# 03-Front_Panel_SFP_1.net
KiCad netlist of a schematic drawn in Altium Designer
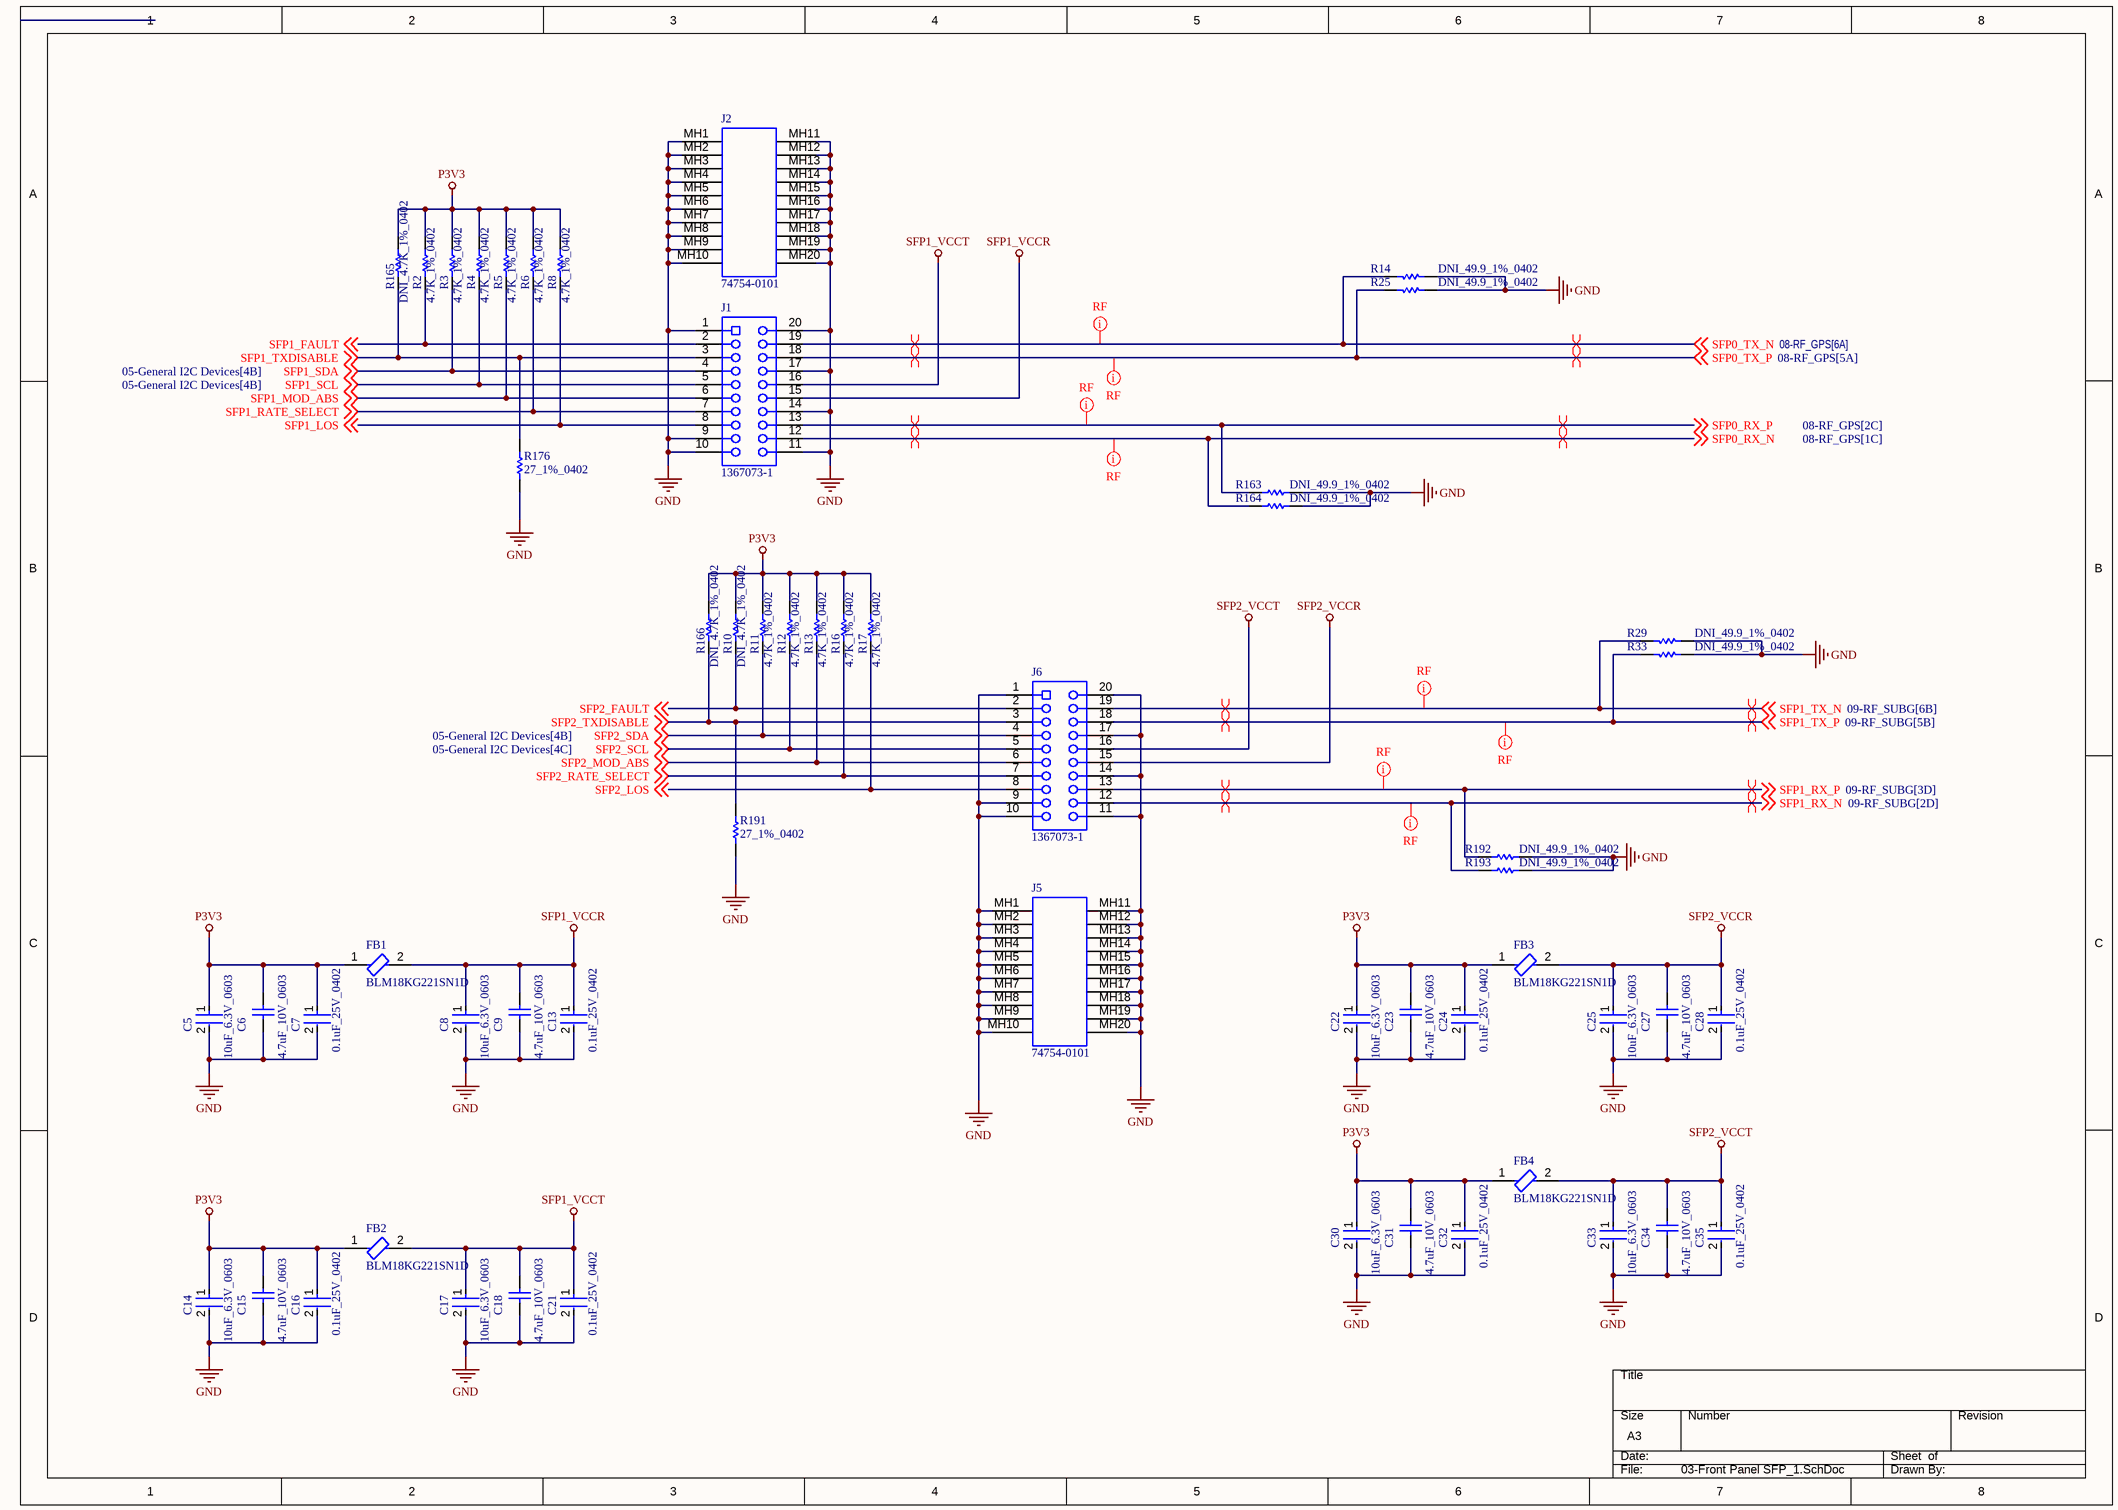
[diagram p0: 03-Front Panel SFP_1.SchDoc]

(export (version "E")
  (design (tool "Eeschema 10.0.6"))
  (components
    (comp (ref "C5")
      (value "10uF_6.3V_0603")
      (footprint "FP-C0603C106M9PACTU-MFG")
      (description "CAP CER 10UF 6.3V X5R 0603")
      (fields
        (field (name "MANUFACTURER PART NUMBER") "C0603C106M9PACTU")
        (field (name "MANUFACTURER") "Kemet")
      )
      (libsource (lib "Altium Content Vault") (part "b4654b650e69147ec39a6b967a45e02"))
    )
    (comp (ref "C6")
      (value "4.7uF_10V_0603")
      (footprint "CAPC1608X87X35NL15T15")
      (fields (field (name "PART NUMBER") "C0603C475K8PACTU") (field (name "MANUFACTURER") "Kemet"))
      (libsource (lib "Altium Content Vault") (part "CAP"))
    )
    (comp (ref "C7")
      (value "0.1uF_25V_0402")
      (footprint "FP-0402-L_1_0_1-W_0_5_0_1-IPC_C")
      (description "General Purpose Ceramic Capacitor, 0402, 100nF, 10%, X7R, 15%, 25V")
      (fields (field (name "VOLTAGE") "25V") (field (name "TOLERANCE") "10%"))
      (libsource (lib "Altium Content Vault") (part "b4654b650e69147ec39a6b967a45e02"))
    )
    (comp (ref "C8")
      (value "10uF_6.3V_0603")
      (footprint "FP-C0603C106M9PACTU-MFG")
      (description "CAP CER 10UF 6.3V X5R 0603")
      (fields
        (field (name "MANUFACTURER PART NUMBER") "C0603C106M9PACTU")
        (field (name "MANUFACTURER") "Kemet")
      )
      (libsource (lib "Altium Content Vault") (part "b4654b650e69147ec39a6b967a45e02"))
    )
    (comp (ref "C9")
      (value "4.7uF_10V_0603")
      (footprint "CAPC1608X87X35NL15T15")
      (fields (field (name "PART NUMBER") "C0603C475K8PACTU") (field (name "MANUFACTURER") "Kemet"))
      (libsource (lib "Altium Content Vault") (part "CAP"))
    )
    (comp (ref "C13")
      (value "0.1uF_25V_0402")
      (footprint "FP-0402-L_1_0_1-W_0_5_0_1-IPC_C")
      (description "General Purpose Ceramic Capacitor, 0402, 100nF, 10%, X7R, 15%, 25V")
      (fields (field (name "VOLTAGE") "25V") (field (name "TOLERANCE") "10%"))
      (libsource (lib "Altium Content Vault") (part "b4654b650e69147ec39a6b967a45e02"))
    )
    (comp (ref "C14")
      (value "10uF_6.3V_0603")
      (footprint "FP-C0603C106M9PACTU-MFG")
      (description "CAP CER 10UF 6.3V X5R 0603")
      (fields
        (field (name "MANUFACTURER PART NUMBER") "C0603C106M9PACTU")
        (field (name "MANUFACTURER") "Kemet")
      )
      (libsource (lib "Altium Content Vault") (part "b4654b650e69147ec39a6b967a45e02"))
    )
    (comp (ref "C15")
      (value "4.7uF_10V_0603")
      (footprint "CAPC1608X87X35NL15T15")
      (fields (field (name "PART NUMBER") "C0603C475K8PACTU") (field (name "MANUFACTURER") "Kemet"))
      (libsource (lib "Altium Content Vault") (part "CAP"))
    )
    (comp (ref "C16")
      (value "0.1uF_25V_0402")
      (footprint "FP-0402-L_1_0_1-W_0_5_0_1-IPC_C")
      (description "General Purpose Ceramic Capacitor, 0402, 100nF, 10%, X7R, 15%, 25V")
      (fields (field (name "VOLTAGE") "25V") (field (name "TOLERANCE") "10%"))
      (libsource (lib "Altium Content Vault") (part "b4654b650e69147ec39a6b967a45e02"))
    )
    (comp (ref "C17")
      (value "10uF_6.3V_0603")
      (footprint "FP-C0603C106M9PACTU-MFG")
      (description "CAP CER 10UF 6.3V X5R 0603")
      (fields
        (field (name "MANUFACTURER PART NUMBER") "C0603C106M9PACTU")
        (field (name "MANUFACTURER") "Kemet")
      )
      (libsource (lib "Altium Content Vault") (part "b4654b650e69147ec39a6b967a45e02"))
    )
    (comp (ref "C18")
      (value "4.7uF_10V_0603")
      (footprint "CAPC1608X87X35NL15T15")
      (fields (field (name "PART NUMBER") "C0603C475K8PACTU") (field (name "MANUFACTURER") "Kemet"))
      (libsource (lib "Altium Content Vault") (part "CAP"))
    )
    (comp (ref "C21")
      (value "0.1uF_25V_0402")
      (footprint "FP-0402-L_1_0_1-W_0_5_0_1-IPC_C")
      (description "General Purpose Ceramic Capacitor, 0402, 100nF, 10%, X7R, 15%, 25V")
      (fields (field (name "VOLTAGE") "25V") (field (name "TOLERANCE") "10%"))
      (libsource (lib "Altium Content Vault") (part "b4654b650e69147ec39a6b967a45e02"))
    )
    (comp (ref "C22")
      (value "10uF_6.3V_0603")
      (footprint "FP-C0603C106M9PACTU-MFG")
      (description "CAP CER 10UF 6.3V X5R 0603")
      (fields
        (field (name "MANUFACTURER PART NUMBER") "C0603C106M9PACTU")
        (field (name "MANUFACTURER") "Kemet")
      )
      (libsource (lib "Altium Content Vault") (part "b4654b650e69147ec39a6b967a45e02"))
    )
    (comp (ref "C23")
      (value "4.7uF_10V_0603")
      (footprint "CAPC1608X87X35NL15T15")
      (fields (field (name "PART NUMBER") "C0603C475K8PACTU") (field (name "MANUFACTURER") "Kemet"))
      (libsource (lib "Altium Content Vault") (part "CAP"))
    )
    (comp (ref "C24")
      (value "0.1uF_25V_0402")
      (footprint "FP-0402-L_1_0_1-W_0_5_0_1-IPC_C")
      (description "General Purpose Ceramic Capacitor, 0402, 100nF, 10%, X7R, 15%, 25V")
      (fields (field (name "VOLTAGE") "25V") (field (name "TOLERANCE") "10%"))
      (libsource (lib "Altium Content Vault") (part "b4654b650e69147ec39a6b967a45e02"))
    )
    (comp (ref "C25")
      (value "10uF_6.3V_0603")
      (footprint "FP-C0603C106M9PACTU-MFG")
      (description "CAP CER 10UF 6.3V X5R 0603")
      (fields
        (field (name "MANUFACTURER PART NUMBER") "C0603C106M9PACTU")
        (field (name "MANUFACTURER") "Kemet")
      )
      (libsource (lib "Altium Content Vault") (part "b4654b650e69147ec39a6b967a45e02"))
    )
    (comp (ref "C27")
      (value "4.7uF_10V_0603")
      (footprint "CAPC1608X87X35NL15T15")
      (fields (field (name "PART NUMBER") "C0603C475K8PACTU") (field (name "MANUFACTURER") "Kemet"))
      (libsource (lib "Altium Content Vault") (part "CAP"))
    )
    (comp (ref "C28")
      (value "0.1uF_25V_0402")
      (footprint "FP-0402-L_1_0_1-W_0_5_0_1-IPC_C")
      (description "General Purpose Ceramic Capacitor, 0402, 100nF, 10%, X7R, 15%, 25V")
      (fields (field (name "VOLTAGE") "25V") (field (name "TOLERANCE") "10%"))
      (libsource (lib "Altium Content Vault") (part "b4654b650e69147ec39a6b967a45e02"))
    )
    (comp (ref "C30")
      (value "10uF_6.3V_0603")
      (footprint "FP-C0603C106M9PACTU-MFG")
      (description "CAP CER 10UF 6.3V X5R 0603")
      (fields
        (field (name "MANUFACTURER PART NUMBER") "C0603C106M9PACTU")
        (field (name "MANUFACTURER") "Kemet")
      )
      (libsource (lib "Altium Content Vault") (part "b4654b650e69147ec39a6b967a45e02"))
    )
    (comp (ref "C31")
      (value "4.7uF_10V_0603")
      (footprint "CAPC1608X87X35NL15T15")
      (fields (field (name "PART NUMBER") "C0603C475K8PACTU") (field (name "MANUFACTURER") "Kemet"))
      (libsource (lib "Altium Content Vault") (part "CAP"))
    )
    (comp (ref "C32")
      (value "0.1uF_25V_0402")
      (footprint "FP-0402-L_1_0_1-W_0_5_0_1-IPC_C")
      (description "General Purpose Ceramic Capacitor, 0402, 100nF, 10%, X7R, 15%, 25V")
      (fields (field (name "VOLTAGE") "25V") (field (name "TOLERANCE") "10%"))
      (libsource (lib "Altium Content Vault") (part "b4654b650e69147ec39a6b967a45e02"))
    )
    (comp (ref "C33")
      (value "10uF_6.3V_0603")
      (footprint "FP-C0603C106M9PACTU-MFG")
      (description "CAP CER 10UF 6.3V X5R 0603")
      (fields
        (field (name "MANUFACTURER PART NUMBER") "C0603C106M9PACTU")
        (field (name "MANUFACTURER") "Kemet")
      )
      (libsource (lib "Altium Content Vault") (part "b4654b650e69147ec39a6b967a45e02"))
    )
    (comp (ref "C34")
      (value "4.7uF_10V_0603")
      (footprint "CAPC1608X87X35NL15T15")
      (fields (field (name "PART NUMBER") "C0603C475K8PACTU") (field (name "MANUFACTURER") "Kemet"))
      (libsource (lib "Altium Content Vault") (part "CAP"))
    )
    (comp (ref "C35")
      (value "0.1uF_25V_0402")
      (footprint "FP-0402-L_1_0_1-W_0_5_0_1-IPC_C")
      (description "General Purpose Ceramic Capacitor, 0402, 100nF, 10%, X7R, 15%, 25V")
      (fields (field (name "VOLTAGE") "25V") (field (name "TOLERANCE") "10%"))
      (libsource (lib "Altium Content Vault") (part "b4654b650e69147ec39a6b967a45e02"))
    )
    (comp (ref "FB1")
      (value "BLM18KG221SN1D")
      (footprint "FP-BLM18-0_15-t0_8-IPC_B")
      (description "Chip Ferrite Bead, 0603, 220Ω @ 100MHz, 0.05Ω, 25%, 2.2A")
      (fields (field (name "TOLERANCE") "25%"))
      (libsource (lib "Altium Content Vault") (part "5f30dd21d616792df468990f7003faa"))
    )
    (comp (ref "FB2")
      (value "BLM18KG221SN1D")
      (footprint "FP-BLM18-0_15-t0_8-IPC_B")
      (description "Chip Ferrite Bead, 0603, 220Ω @ 100MHz, 0.05Ω, 25%, 2.2A")
      (fields (field (name "TOLERANCE") "25%"))
      (libsource (lib "Altium Content Vault") (part "5f30dd21d616792df468990f7003faa"))
    )
    (comp (ref "FB3")
      (value "BLM18KG221SN1D")
      (footprint "FP-BLM18-0_15-t0_8-IPC_B")
      (description "Chip Ferrite Bead, 0603, 220Ω @ 100MHz, 0.05Ω, 25%, 2.2A")
      (fields (field (name "TOLERANCE") "25%"))
      (libsource (lib "Altium Content Vault") (part "5f30dd21d616792df468990f7003faa"))
    )
    (comp (ref "FB4")
      (value "BLM18KG221SN1D")
      (footprint "FP-BLM18-0_15-t0_8-IPC_B")
      (description "Chip Ferrite Bead, 0603, 220Ω @ 100MHz, 0.05Ω, 25%, 2.2A")
      (fields (field (name "TOLERANCE") "25%"))
      (libsource (lib "Altium Content Vault") (part "5f30dd21d616792df468990f7003faa"))
    )
    (comp (ref "J1")
      (value "1367073-1")
      (footprint "TECO-1367073-1_V")
      (fields (field (name "MANUFACTURER") "TE Connectivity"))
      (libsource (lib "Altium Content Vault") (part "CN-2P-F-R20_B"))
    )
    (comp (ref "J2")
      (value "74754-0101")
      (footprint "MOLX-74754-0101_V")
      (description "SFP+ Cage, Single Port, Height 10.85 mm, Tail Height 3.05 mm, -40 to 85 degC, RoHS, Tray")
      (libsource (lib "Altium Content Vault") (part "MOLX-74754-0101"))
    )
    (comp (ref "J5")
      (value "74754-0101")
      (footprint "MOLX-74754-0101_V")
      (description "SFP+ Cage, Single Port, Height 10.85 mm, Tail Height 3.05 mm, -40 to 85 degC, RoHS, Tray")
      (libsource (lib "Altium Content Vault") (part "MOLX-74754-0101"))
    )
    (comp (ref "J6")
      (value "1367073-1")
      (footprint "TECO-1367073-1_V")
      (fields (field (name "MANUFACTURER") "TE Connectivity"))
      (libsource (lib "Altium Content Vault") (part "CN-2P-F-R20_B"))
    )
    (comp (ref "R2")
      (value "4.7K_1%_0402")
      (footprint "RESC1005X40X25NL10T10")
      (fields (field (name "MANUFACTURER") "Bourns") (field (name "PART NUMBER") "CR0402-FX-4701GLF"))
      (libsource (lib "Altium Content Vault") (part "RES"))
    )
    (comp (ref "R3")
      (value "4.7K_1%_0402")
      (footprint "RESC1005X40X25NL10T10")
      (fields (field (name "MANUFACTURER") "Bourns") (field (name "PART NUMBER") "CR0402-FX-4701GLF"))
      (libsource (lib "Altium Content Vault") (part "RES"))
    )
    (comp (ref "R4")
      (value "4.7K_1%_0402")
      (footprint "RESC1005X40X25NL10T10")
      (fields (field (name "MANUFACTURER") "Bourns") (field (name "PART NUMBER") "CR0402-FX-4701GLF"))
      (libsource (lib "Altium Content Vault") (part "RES"))
    )
    (comp (ref "R5")
      (value "4.7K_1%_0402")
      (footprint "RESC1005X40X25NL10T10")
      (fields (field (name "MANUFACTURER") "Bourns") (field (name "PART NUMBER") "CR0402-FX-4701GLF"))
      (libsource (lib "Altium Content Vault") (part "RES"))
    )
    (comp (ref "R6")
      (value "4.7K_1%_0402")
      (footprint "RESC1005X40X25NL10T10")
      (fields (field (name "MANUFACTURER") "Bourns") (field (name "PART NUMBER") "CR0402-FX-4701GLF"))
      (libsource (lib "Altium Content Vault") (part "RES"))
    )
    (comp (ref "R8")
      (value "4.7K_1%_0402")
      (footprint "RESC1005X40X25NL10T10")
      (fields (field (name "MANUFACTURER") "Bourns") (field (name "PART NUMBER") "CR0402-FX-4701GLF"))
      (libsource (lib "Altium Content Vault") (part "RES"))
    )
    (comp (ref "R10")
      (value "DNI_4.7K_1%_0402")
      (footprint "RESC1005X40X25NL10T10")
      (fields (field (name "MANUFACTURER") "Bourns") (field (name "PART NUMBER") "CR0402-FX-4701GLF"))
      (libsource (lib "Altium Content Vault") (part "RES"))
    )
    (comp (ref "R11")
      (value "4.7K_1%_0402")
      (footprint "RESC1005X40X25NL10T10")
      (fields (field (name "MANUFACTURER") "Bourns") (field (name "PART NUMBER") "CR0402-FX-4701GLF"))
      (libsource (lib "Altium Content Vault") (part "RES"))
    )
    (comp (ref "R12")
      (value "4.7K_1%_0402")
      (footprint "RESC1005X40X25NL10T10")
      (fields (field (name "MANUFACTURER") "Bourns") (field (name "PART NUMBER") "CR0402-FX-4701GLF"))
      (libsource (lib "Altium Content Vault") (part "RES"))
    )
    (comp (ref "R13")
      (value "4.7K_1%_0402")
      (footprint "RESC1005X40X25NL10T10")
      (fields (field (name "MANUFACTURER") "Bourns") (field (name "PART NUMBER") "CR0402-FX-4701GLF"))
      (libsource (lib "Altium Content Vault") (part "RES"))
    )
    (comp (ref "R14")
      (value "DNI_49.9_1%_0402")
      (footprint "RESC1005X40X25NL10T10")
      (fields (field (name "PART NUMBER") "RK73H1ETTP49R9F") (field (name "MANUFACTURER") "KOA Speer"))
      (libsource (lib "Altium Content Vault") (part "RES"))
    )
    (comp (ref "R16")
      (value "4.7K_1%_0402")
      (footprint "RESC1005X40X25NL10T10")
      (fields (field (name "MANUFACTURER") "Bourns") (field (name "PART NUMBER") "CR0402-FX-4701GLF"))
      (libsource (lib "Altium Content Vault") (part "RES"))
    )
    (comp (ref "R17")
      (value "4.7K_1%_0402")
      (footprint "RESC1005X40X25NL10T10")
      (fields (field (name "MANUFACTURER") "Bourns") (field (name "PART NUMBER") "CR0402-FX-4701GLF"))
      (libsource (lib "Altium Content Vault") (part "RES"))
    )
    (comp (ref "R25")
      (value "DNI_49.9_1%_0402")
      (footprint "RESC1005X40X25NL10T10")
      (fields (field (name "PART NUMBER") "RK73H1ETTP49R9F") (field (name "MANUFACTURER") "KOA Speer"))
      (libsource (lib "Altium Content Vault") (part "RES"))
    )
    (comp (ref "R29")
      (value "DNI_49.9_1%_0402")
      (footprint "RESC1005X40X25NL10T10")
      (fields (field (name "PART NUMBER") "RK73H1ETTP49R9F") (field (name "MANUFACTURER") "KOA Speer"))
      (libsource (lib "Altium Content Vault") (part "RES"))
    )
    (comp (ref "R33")
      (value "DNI_49.9_1%_0402")
      (footprint "RESC1005X40X25NL10T10")
      (fields (field (name "PART NUMBER") "RK73H1ETTP49R9F") (field (name "MANUFACTURER") "KOA Speer"))
      (libsource (lib "Altium Content Vault") (part "RES"))
    )
    (comp (ref "R163")
      (value "DNI_49.9_1%_0402")
      (footprint "RESC1005X40X25NL10T10")
      (fields (field (name "PART NUMBER") "RK73H1ETTP49R9F") (field (name "MANUFACTURER") "KOA Speer"))
      (libsource (lib "Altium Content Vault") (part "RES"))
    )
    (comp (ref "R164")
      (value "DNI_49.9_1%_0402")
      (footprint "RESC1005X40X25NL10T10")
      (fields (field (name "PART NUMBER") "RK73H1ETTP49R9F") (field (name "MANUFACTURER") "KOA Speer"))
      (libsource (lib "Altium Content Vault") (part "RES"))
    )
    (comp (ref "R165")
      (value "DNI_4.7K_1%_0402")
      (footprint "RESC1005X40X25NL10T10")
      (fields (field (name "MANUFACTURER") "Bourns") (field (name "PART NUMBER") "CR0402-FX-4701GLF"))
      (libsource (lib "Altium Content Vault") (part "RES"))
    )
    (comp (ref "R166")
      (value "DNI_4.7K_1%_0402")
      (footprint "RESC1005X40X25NL10T10")
      (fields (field (name "MANUFACTURER") "Bourns") (field (name "PART NUMBER") "CR0402-FX-4701GLF"))
      (libsource (lib "Altium Content Vault") (part "RES"))
    )
    (comp (ref "R176")
      (value "27_1%_0402")
      (footprint "RESC1005X40X25NL05T05")
      (fields (field (name "PART NUMBER") "CRCW040227R0FKED") (field (name "MANUFACTURER") "Vishay Dale"))
      (libsource (lib "Altium Content Vault") (part "RES"))
    )
    (comp (ref "R191")
      (value "27_1%_0402")
      (footprint "RESC1005X40X25NL05T05")
      (fields (field (name "PART NUMBER") "CRCW040227R0FKED") (field (name "MANUFACTURER") "Vishay Dale"))
      (libsource (lib "Altium Content Vault") (part "RES"))
    )
    (comp (ref "R192")
      (value "DNI_49.9_1%_0402")
      (footprint "RESC1005X40X25NL10T10")
      (fields (field (name "PART NUMBER") "RK73H1ETTP49R9F") (field (name "MANUFACTURER") "KOA Speer"))
      (libsource (lib "Altium Content Vault") (part "RES"))
    )
    (comp (ref "R193")
      (value "DNI_49.9_1%_0402")
      (footprint "RESC1005X40X25NL10T10")
      (fields (field (name "PART NUMBER") "RK73H1ETTP49R9F") (field (name "MANUFACTURER") "KOA Speer"))
      (libsource (lib "Altium Content Vault") (part "RES"))
    )
  )
  (nets
    (net (code "1") (name "GND") (class "Default")
      (node (ref "C13") (pin "2") (pinfunction "2_2") (pintype "passive"))
      (node (ref "C14") (pin "2") (pinfunction "2_2") (pintype "passive"))
      (node (ref "C15") (pin "1") (pinfunction "1_1") (pintype "passive"))
      (node (ref "C16") (pin "2") (pinfunction "2_2") (pintype "passive"))
      (node (ref "C17") (pin "2") (pinfunction "2_2") (pintype "passive"))
      (node (ref "C18") (pin "1") (pinfunction "1_1") (pintype "passive"))
      (node (ref "C21") (pin "2") (pinfunction "2_2") (pintype "passive"))
      (node (ref "C22") (pin "2") (pinfunction "2_2") (pintype "passive"))
      (node (ref "C23") (pin "1") (pinfunction "1_1") (pintype "passive"))
      (node (ref "C24") (pin "2") (pinfunction "2_2") (pintype "passive"))
      (node (ref "C25") (pin "2") (pinfunction "2_2") (pintype "passive"))
      (node (ref "C27") (pin "1") (pinfunction "1_1") (pintype "passive"))
      (node (ref "C28") (pin "2") (pinfunction "2_2") (pintype "passive"))
      (node (ref "C30") (pin "2") (pinfunction "2_2") (pintype "passive"))
      (node (ref "C31") (pin "1") (pinfunction "1_1") (pintype "passive"))
      (node (ref "C32") (pin "2") (pinfunction "2_2") (pintype "passive"))
      (node (ref "C33") (pin "2") (pinfunction "2_2") (pintype "passive"))
      (node (ref "C34") (pin "1") (pinfunction "1_1") (pintype "passive"))
      (node (ref "C35") (pin "2") (pinfunction "2_2") (pintype "passive"))
      (node (ref "C5") (pin "2") (pinfunction "2_2") (pintype "passive"))
      (node (ref "C6") (pin "1") (pinfunction "1_1") (pintype "passive"))
      (node (ref "C7") (pin "2") (pinfunction "2_2") (pintype "passive"))
      (node (ref "C8") (pin "2") (pinfunction "2_2") (pintype "passive"))
      (node (ref "C9") (pin "1") (pinfunction "1_1") (pintype "passive"))
      (node (ref "J1") (pin "1") (pinfunction "1_1") (pintype "passive"))
      (node (ref "J1") (pin "10") (pinfunction "10_10") (pintype "passive"))
      (node (ref "J1") (pin "11") (pinfunction "11_11") (pintype "passive"))
      (node (ref "J1") (pin "14") (pinfunction "14_14") (pintype "passive"))
      (node (ref "J1") (pin "17") (pinfunction "17_17") (pintype "passive"))
      (node (ref "J1") (pin "20") (pinfunction "20_20") (pintype "passive"))
      (node (ref "J1") (pin "9") (pinfunction "9_9") (pintype "passive"))
      (node (ref "J2") (pin "MH1") (pinfunction "MH1_MH1") (pintype "passive"))
      (node (ref "J2") (pin "MH10") (pinfunction "MH10_MH10") (pintype "passive"))
      (node (ref "J2") (pin "MH11") (pinfunction "MH11_MH11") (pintype "passive"))
      (node (ref "J2") (pin "MH12") (pinfunction "MH12_MH12") (pintype "passive"))
      (node (ref "J2") (pin "MH13") (pinfunction "MH13_MH13") (pintype "passive"))
      (node (ref "J2") (pin "MH14") (pinfunction "MH14_MH14") (pintype "passive"))
      (node (ref "J2") (pin "MH15") (pinfunction "MH15_MH15") (pintype "passive"))
      (node (ref "J2") (pin "MH16") (pinfunction "MH16_MH16") (pintype "passive"))
      (node (ref "J2") (pin "MH17") (pinfunction "MH17_MH17") (pintype "passive"))
      (node (ref "J2") (pin "MH18") (pinfunction "MH18_MH18") (pintype "passive"))
      (node (ref "J2") (pin "MH19") (pinfunction "MH19_MH19") (pintype "passive"))
      (node (ref "J2") (pin "MH2") (pinfunction "MH2_MH2") (pintype "passive"))
      (node (ref "J2") (pin "MH20") (pinfunction "MH20_MH20") (pintype "passive"))
      (node (ref "J2") (pin "MH3") (pinfunction "MH3_MH3") (pintype "passive"))
      (node (ref "J2") (pin "MH4") (pinfunction "MH4_MH4") (pintype "passive"))
      (node (ref "J2") (pin "MH5") (pinfunction "MH5_MH5") (pintype "passive"))
      (node (ref "J2") (pin "MH6") (pinfunction "MH6_MH6") (pintype "passive"))
      (node (ref "J2") (pin "MH7") (pinfunction "MH7_MH7") (pintype "passive"))
      (node (ref "J2") (pin "MH8") (pinfunction "MH8_MH8") (pintype "passive"))
      (node (ref "J2") (pin "MH9") (pinfunction "MH9_MH9") (pintype "passive"))
      (node (ref "J5") (pin "MH1") (pinfunction "MH1_MH1") (pintype "passive"))
      (node (ref "J5") (pin "MH10") (pinfunction "MH10_MH10") (pintype "passive"))
      (node (ref "J5") (pin "MH11") (pinfunction "MH11_MH11") (pintype "passive"))
      (node (ref "J5") (pin "MH12") (pinfunction "MH12_MH12") (pintype "passive"))
      (node (ref "J5") (pin "MH13") (pinfunction "MH13_MH13") (pintype "passive"))
      (node (ref "J5") (pin "MH14") (pinfunction "MH14_MH14") (pintype "passive"))
      (node (ref "J5") (pin "MH15") (pinfunction "MH15_MH15") (pintype "passive"))
      (node (ref "J5") (pin "MH16") (pinfunction "MH16_MH16") (pintype "passive"))
      (node (ref "J5") (pin "MH17") (pinfunction "MH17_MH17") (pintype "passive"))
      (node (ref "J5") (pin "MH18") (pinfunction "MH18_MH18") (pintype "passive"))
      (node (ref "J5") (pin "MH19") (pinfunction "MH19_MH19") (pintype "passive"))
      (node (ref "J5") (pin "MH2") (pinfunction "MH2_MH2") (pintype "passive"))
      (node (ref "J5") (pin "MH20") (pinfunction "MH20_MH20") (pintype "passive"))
      (node (ref "J5") (pin "MH3") (pinfunction "MH3_MH3") (pintype "passive"))
      (node (ref "J5") (pin "MH4") (pinfunction "MH4_MH4") (pintype "passive"))
      (node (ref "J5") (pin "MH5") (pinfunction "MH5_MH5") (pintype "passive"))
      (node (ref "J5") (pin "MH6") (pinfunction "MH6_MH6") (pintype "passive"))
      (node (ref "J5") (pin "MH7") (pinfunction "MH7_MH7") (pintype "passive"))
      (node (ref "J5") (pin "MH8") (pinfunction "MH8_MH8") (pintype "passive"))
      (node (ref "J5") (pin "MH9") (pinfunction "MH9_MH9") (pintype "passive"))
      (node (ref "J6") (pin "1") (pinfunction "1_1") (pintype "passive"))
      (node (ref "J6") (pin "10") (pinfunction "10_10") (pintype "passive"))
      (node (ref "J6") (pin "11") (pinfunction "11_11") (pintype "passive"))
      (node (ref "J6") (pin "14") (pinfunction "14_14") (pintype "passive"))
      (node (ref "J6") (pin "17") (pinfunction "17_17") (pintype "passive"))
      (node (ref "J6") (pin "20") (pinfunction "20_20") (pintype "passive"))
      (node (ref "J6") (pin "9") (pinfunction "9_9") (pintype "passive"))
      (node (ref "R14") (pin "2") (pinfunction "2_2") (pintype "passive"))
      (node (ref "R163") (pin "2") (pinfunction "2_2") (pintype "passive"))
      (node (ref "R164") (pin "2") (pinfunction "2_2") (pintype "passive"))
      (node (ref "R176") (pin "1") (pinfunction "1_1") (pintype "passive"))
      (node (ref "R191") (pin "1") (pinfunction "1_1") (pintype "passive"))
      (node (ref "R192") (pin "2") (pinfunction "2_2") (pintype "passive"))
      (node (ref "R193") (pin "2") (pinfunction "2_2") (pintype "passive"))
      (node (ref "R25") (pin "2") (pinfunction "2_2") (pintype "passive"))
      (node (ref "R29") (pin "2") (pinfunction "2_2") (pintype "passive"))
      (node (ref "R33") (pin "2") (pinfunction "2_2") (pintype "passive"))
    )
    (net (code "2") (name "P3V3") (class "Default")
      (node (ref "C14") (pin "1") (pinfunction "1_1") (pintype "passive"))
      (node (ref "C15") (pin "2") (pinfunction "2_2") (pintype "passive"))
      (node (ref "C16") (pin "1") (pinfunction "1_1") (pintype "passive"))
      (node (ref "C22") (pin "1") (pinfunction "1_1") (pintype "passive"))
      (node (ref "C23") (pin "2") (pinfunction "2_2") (pintype "passive"))
      (node (ref "C24") (pin "1") (pinfunction "1_1") (pintype "passive"))
      (node (ref "C30") (pin "1") (pinfunction "1_1") (pintype "passive"))
      (node (ref "C31") (pin "2") (pinfunction "2_2") (pintype "passive"))
      (node (ref "C32") (pin "1") (pinfunction "1_1") (pintype "passive"))
      (node (ref "C5") (pin "1") (pinfunction "1_1") (pintype "passive"))
      (node (ref "C6") (pin "2") (pinfunction "2_2") (pintype "passive"))
      (node (ref "C7") (pin "1") (pinfunction "1_1") (pintype "passive"))
      (node (ref "FB1") (pin "1") (pinfunction "1_1") (pintype "passive"))
      (node (ref "FB2") (pin "1") (pinfunction "1_1") (pintype "passive"))
      (node (ref "FB3") (pin "1") (pinfunction "1_1") (pintype "passive"))
      (node (ref "FB4") (pin "1") (pinfunction "1_1") (pintype "passive"))
      (node (ref "R10") (pin "1") (pinfunction "1_1") (pintype "passive"))
      (node (ref "R11") (pin "1") (pinfunction "1_1") (pintype "passive"))
      (node (ref "R12") (pin "1") (pinfunction "1_1") (pintype "passive"))
      (node (ref "R13") (pin "1") (pinfunction "1_1") (pintype "passive"))
      (node (ref "R16") (pin "1") (pinfunction "1_1") (pintype "passive"))
      (node (ref "R165") (pin "1") (pinfunction "1_1") (pintype "passive"))
      (node (ref "R166") (pin "1") (pinfunction "1_1") (pintype "passive"))
      (node (ref "R17") (pin "1") (pinfunction "1_1") (pintype "passive"))
      (node (ref "R2") (pin "1") (pinfunction "1_1") (pintype "passive"))
      (node (ref "R3") (pin "1") (pinfunction "1_1") (pintype "passive"))
      (node (ref "R4") (pin "1") (pinfunction "1_1") (pintype "passive"))
      (node (ref "R5") (pin "1") (pinfunction "1_1") (pintype "passive"))
      (node (ref "R6") (pin "1") (pinfunction "1_1") (pintype "passive"))
      (node (ref "R8") (pin "1") (pinfunction "1_1") (pintype "passive"))
    )
    (net (code "3") (name "SFP0_RX_N") (class "Default")
      (node (ref "J1") (pin "12") (pinfunction "12_12") (pintype "passive"))
      (node (ref "R164") (pin "1") (pinfunction "1_1") (pintype "passive"))
    )
    (net (code "4") (name "SFP0_RX_P") (class "Default")
      (node (ref "J1") (pin "13") (pinfunction "13_13") (pintype "passive"))
      (node (ref "R163") (pin "1") (pinfunction "1_1") (pintype "passive"))
    )
    (net (code "5") (name "SFP0_TX_N") (class "Default")
      (node (ref "J1") (pin "19") (pinfunction "19_19") (pintype "passive"))
      (node (ref "R14") (pin "1") (pinfunction "1_1") (pintype "passive"))
    )
    (net (code "6") (name "SFP0_TX_P") (class "Default")
      (node (ref "J1") (pin "18") (pinfunction "18_18") (pintype "passive"))
      (node (ref "R25") (pin "1") (pinfunction "1_1") (pintype "passive"))
    )
    (net (code "7") (name "SFP1_FAULT") (class "Default")
      (node (ref "J1") (pin "2") (pinfunction "2_2") (pintype "passive"))
      (node (ref "R2") (pin "2") (pinfunction "2_2") (pintype "passive"))
    )
    (net (code "8") (name "SFP1_LOS") (class "Default")
      (node (ref "J1") (pin "8") (pinfunction "8_8") (pintype "passive"))
      (node (ref "R8") (pin "2") (pinfunction "2_2") (pintype "passive"))
    )
    (net (code "9") (name "SFP1_MOD_ABS") (class "Default")
      (node (ref "J1") (pin "6") (pinfunction "6_6") (pintype "passive"))
      (node (ref "R5") (pin "2") (pinfunction "2_2") (pintype "passive"))
    )
    (net (code "10") (name "SFP1_RATE_SELECT") (class "Default")
      (node (ref "J1") (pin "7") (pinfunction "7_7") (pintype "passive"))
      (node (ref "R6") (pin "2") (pinfunction "2_2") (pintype "passive"))
    )
    (net (code "11") (name "SFP1_RX_N") (class "Default")
      (node (ref "J6") (pin "12") (pinfunction "12_12") (pintype "passive"))
      (node (ref "R193") (pin "1") (pinfunction "1_1") (pintype "passive"))
    )
    (net (code "12") (name "SFP1_RX_P") (class "Default")
      (node (ref "J6") (pin "13") (pinfunction "13_13") (pintype "passive"))
      (node (ref "R192") (pin "1") (pinfunction "1_1") (pintype "passive"))
    )
    (net (code "13") (name "SFP1_SCL") (class "Default")
      (node (ref "J1") (pin "5") (pinfunction "5_5") (pintype "passive"))
      (node (ref "R4") (pin "2") (pinfunction "2_2") (pintype "passive"))
    )
    (net (code "14") (name "SFP1_SDA") (class "Default")
      (node (ref "J1") (pin "4") (pinfunction "4_4") (pintype "passive"))
      (node (ref "R3") (pin "2") (pinfunction "2_2") (pintype "passive"))
    )
    (net (code "15") (name "SFP1_TXDISABLE") (class "Default")
      (node (ref "J1") (pin "3") (pinfunction "3_3") (pintype "passive"))
      (node (ref "R165") (pin "2") (pinfunction "2_2") (pintype "passive"))
      (node (ref "R176") (pin "2") (pinfunction "2_2") (pintype "passive"))
    )
    (net (code "16") (name "SFP1_TX_N") (class "Default")
      (node (ref "J6") (pin "19") (pinfunction "19_19") (pintype "passive"))
      (node (ref "R29") (pin "1") (pinfunction "1_1") (pintype "passive"))
    )
    (net (code "17") (name "SFP1_TX_P") (class "Default")
      (node (ref "J6") (pin "18") (pinfunction "18_18") (pintype "passive"))
      (node (ref "R33") (pin "1") (pinfunction "1_1") (pintype "passive"))
    )
    (net (code "18") (name "SFP1_VCCR") (class "Default")
      (node (ref "C13") (pin "1") (pinfunction "1_1") (pintype "passive"))
      (node (ref "C8") (pin "1") (pinfunction "1_1") (pintype "passive"))
      (node (ref "C9") (pin "2") (pinfunction "2_2") (pintype "passive"))
      (node (ref "FB1") (pin "2") (pinfunction "2_2") (pintype "passive"))
      (node (ref "J1") (pin "15") (pinfunction "15_15") (pintype "passive"))
    )
    (net (code "19") (name "SFP1_VCCT") (class "Default")
      (node (ref "C17") (pin "1") (pinfunction "1_1") (pintype "passive"))
      (node (ref "C18") (pin "2") (pinfunction "2_2") (pintype "passive"))
      (node (ref "C21") (pin "1") (pinfunction "1_1") (pintype "passive"))
      (node (ref "FB2") (pin "2") (pinfunction "2_2") (pintype "passive"))
      (node (ref "J1") (pin "16") (pinfunction "16_16") (pintype "passive"))
    )
    (net (code "20") (name "SFP2_FAULT") (class "Default")
      (node (ref "J6") (pin "2") (pinfunction "2_2") (pintype "passive"))
      (node (ref "R10") (pin "2") (pinfunction "2_2") (pintype "passive"))
    )
    (net (code "21") (name "SFP2_LOS") (class "Default")
      (node (ref "J6") (pin "8") (pinfunction "8_8") (pintype "passive"))
      (node (ref "R17") (pin "2") (pinfunction "2_2") (pintype "passive"))
    )
    (net (code "22") (name "SFP2_MOD_ABS") (class "Default")
      (node (ref "J6") (pin "6") (pinfunction "6_6") (pintype "passive"))
      (node (ref "R13") (pin "2") (pinfunction "2_2") (pintype "passive"))
    )
    (net (code "23") (name "SFP2_RATE_SELECT") (class "Default")
      (node (ref "J6") (pin "7") (pinfunction "7_7") (pintype "passive"))
      (node (ref "R16") (pin "2") (pinfunction "2_2") (pintype "passive"))
    )
    (net (code "24") (name "SFP2_SCL") (class "Default")
      (node (ref "J6") (pin "5") (pinfunction "5_5") (pintype "passive"))
      (node (ref "R12") (pin "2") (pinfunction "2_2") (pintype "passive"))
    )
    (net (code "25") (name "SFP2_SDA") (class "Default")
      (node (ref "J6") (pin "4") (pinfunction "4_4") (pintype "passive"))
      (node (ref "R11") (pin "2") (pinfunction "2_2") (pintype "passive"))
    )
    (net (code "26") (name "SFP2_TXDISABLE") (class "Default")
      (node (ref "J6") (pin "3") (pinfunction "3_3") (pintype "passive"))
      (node (ref "R166") (pin "2") (pinfunction "2_2") (pintype "passive"))
      (node (ref "R191") (pin "2") (pinfunction "2_2") (pintype "passive"))
    )
    (net (code "27") (name "SFP2_VCCR") (class "Default")
      (node (ref "C25") (pin "1") (pinfunction "1_1") (pintype "passive"))
      (node (ref "C27") (pin "2") (pinfunction "2_2") (pintype "passive"))
      (node (ref "C28") (pin "1") (pinfunction "1_1") (pintype "passive"))
      (node (ref "FB3") (pin "2") (pinfunction "2_2") (pintype "passive"))
      (node (ref "J6") (pin "15") (pinfunction "15_15") (pintype "passive"))
    )
    (net (code "28") (name "SFP2_VCCT") (class "Default")
      (node (ref "C33") (pin "1") (pinfunction "1_1") (pintype "passive"))
      (node (ref "C34") (pin "2") (pinfunction "2_2") (pintype "passive"))
      (node (ref "C35") (pin "1") (pinfunction "1_1") (pintype "passive"))
      (node (ref "FB4") (pin "2") (pinfunction "2_2") (pintype "passive"))
      (node (ref "J6") (pin "16") (pinfunction "16_16") (pintype "passive"))
    )
  )
)
